# RadioPanel.net
KiCad netlist of a schematic drawn in EAGLE
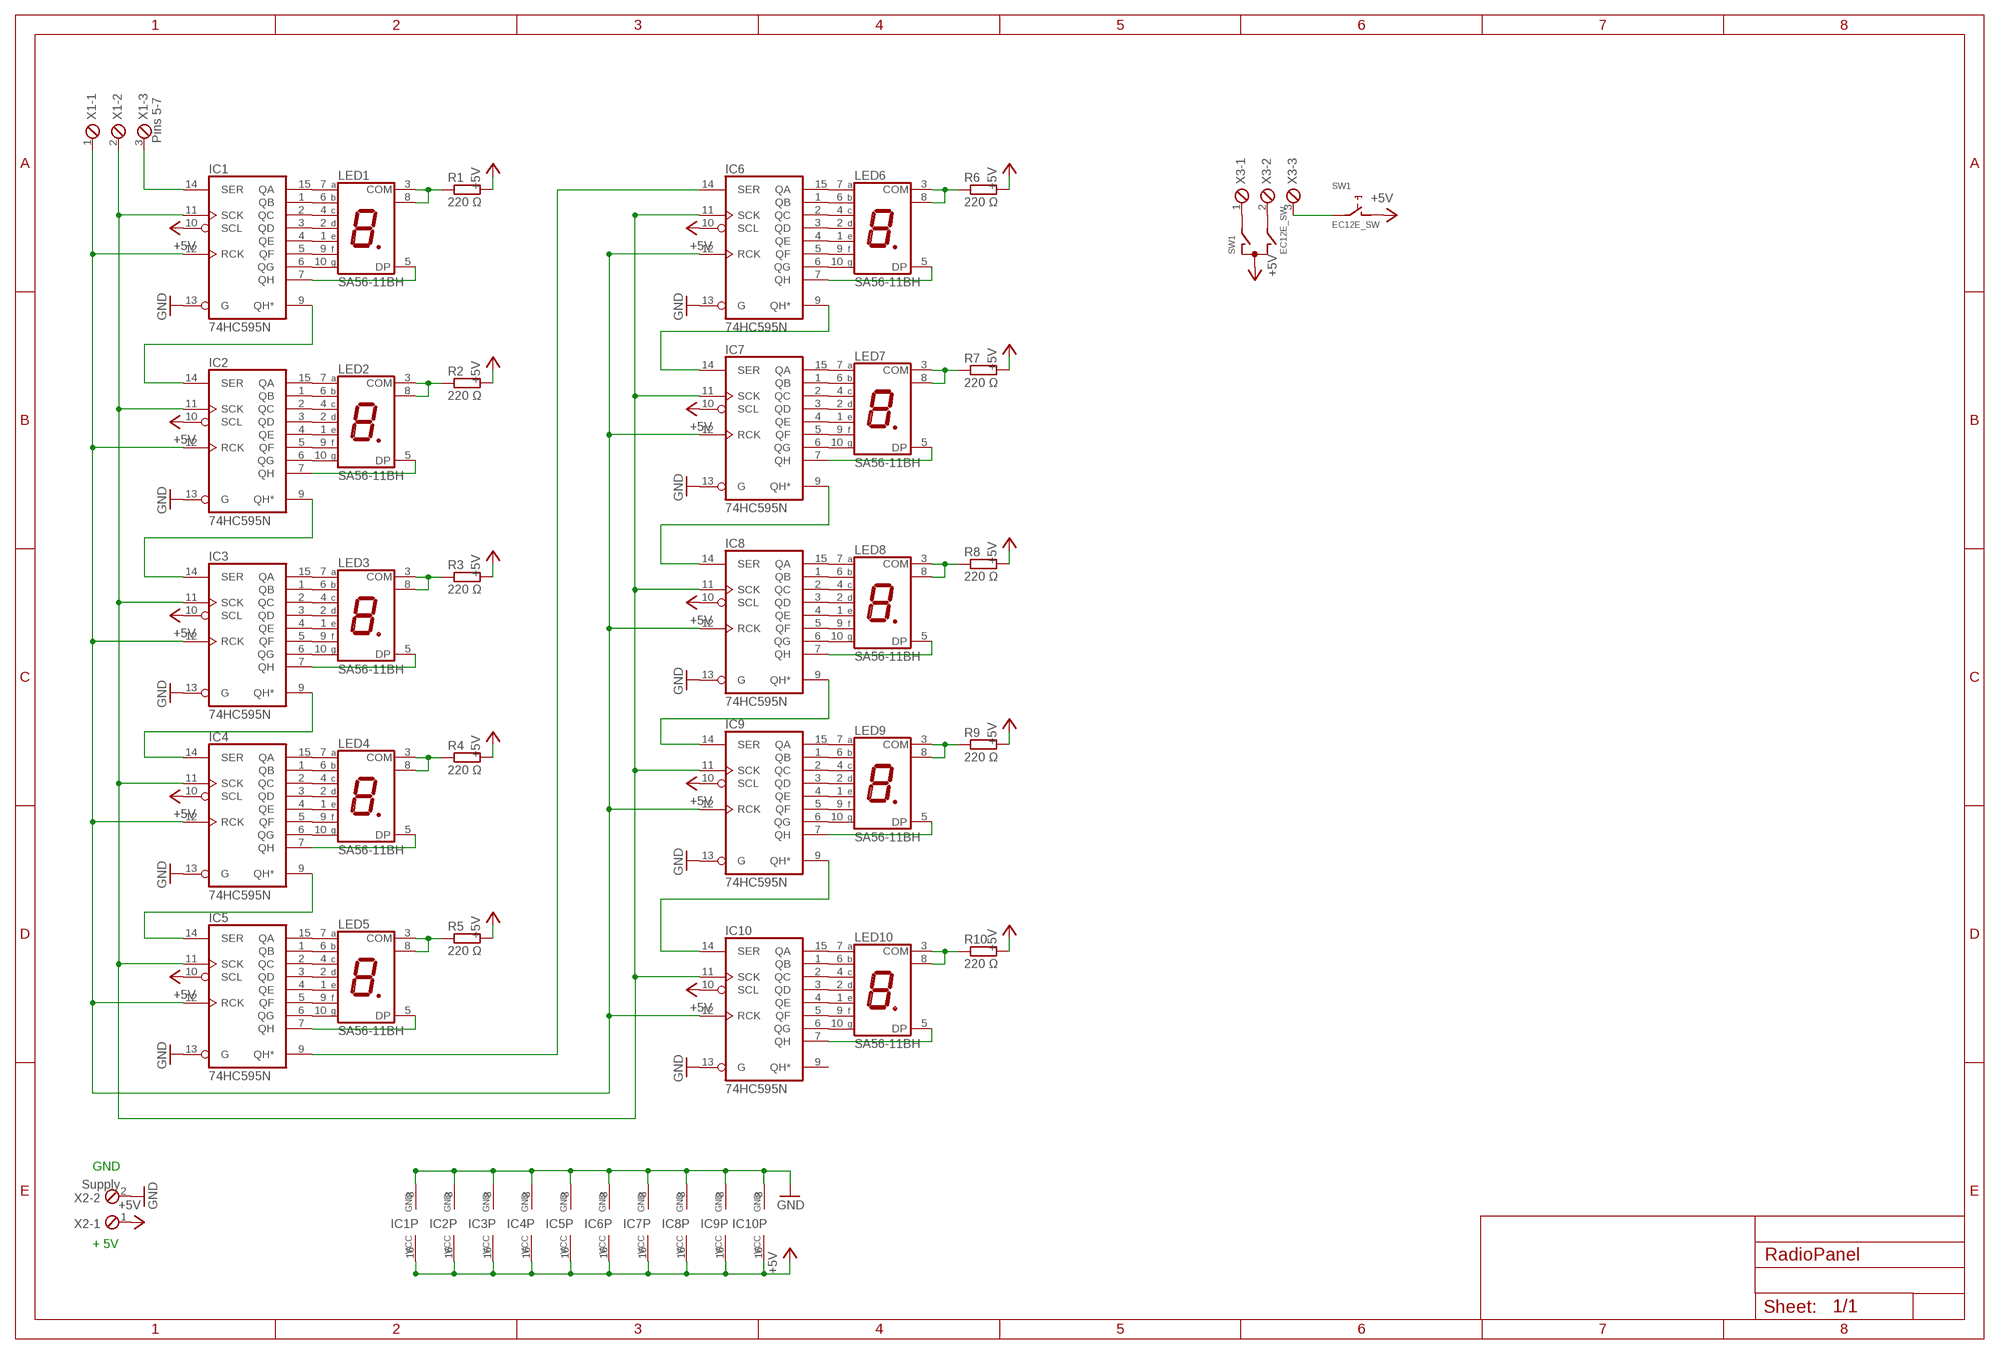
[diagram p0: schematic, sheet 1]

(export (version "E")
  (design (tool "Eeschema 10.0.6"))
  (components
    (comp (ref "IC1")
      (value "74HC595N")
      (footprint "eagle-import:DIL16")
      (libsource (lib "eagle-import") (part "74595NHC"))
    )
    (comp (ref "IC2")
      (value "74HC595N")
      (footprint "eagle-import:DIL16")
      (libsource (lib "eagle-import") (part "74595NHC"))
    )
    (comp (ref "IC3")
      (value "74HC595N")
      (footprint "eagle-import:DIL16")
      (libsource (lib "eagle-import") (part "74595NHC"))
    )
    (comp (ref "IC4")
      (value "74HC595N")
      (footprint "eagle-import:DIL16")
      (libsource (lib "eagle-import") (part "74595NHC"))
    )
    (comp (ref "IC5")
      (value "74HC595N")
      (footprint "eagle-import:DIL16")
      (libsource (lib "eagle-import") (part "74595NHC"))
    )
    (comp (ref "IC6")
      (value "74HC595N")
      (footprint "eagle-import:DIL16")
      (libsource (lib "eagle-import") (part "74595NHC"))
    )
    (comp (ref "IC7")
      (value "74HC595N")
      (footprint "eagle-import:DIL16")
      (libsource (lib "eagle-import") (part "74595NHC"))
    )
    (comp (ref "IC8")
      (value "74HC595N")
      (footprint "eagle-import:DIL16")
      (libsource (lib "eagle-import") (part "74595NHC"))
    )
    (comp (ref "IC9")
      (value "74HC595N")
      (footprint "eagle-import:DIL16")
      (libsource (lib "eagle-import") (part "74595NHC"))
    )
    (comp (ref "IC10")
      (value "74HC595N")
      (footprint "eagle-import:DIL16")
      (libsource (lib "eagle-import") (part "74595NHC"))
    )
    (comp (ref "LED1")
      (value "SA56-11BH")
      (footprint "eagle-import:SA56-11")
      (libsource (lib "eagle-import") (part "7-SEG_SA56-11"))
    )
    (comp (ref "LED2")
      (value "SA56-11BH")
      (footprint "eagle-import:SA56-11")
      (libsource (lib "eagle-import") (part "7-SEG_SA56-11"))
    )
    (comp (ref "LED3")
      (value "SA56-11BH")
      (footprint "eagle-import:SA56-11")
      (libsource (lib "eagle-import") (part "7-SEG_SA56-11"))
    )
    (comp (ref "LED4")
      (value "SA56-11BH")
      (footprint "eagle-import:SA56-11")
      (libsource (lib "eagle-import") (part "7-SEG_SA56-11"))
    )
    (comp (ref "LED5")
      (value "SA56-11BH")
      (footprint "eagle-import:SA56-11")
      (libsource (lib "eagle-import") (part "7-SEG_SA56-11"))
    )
    (comp (ref "LED6")
      (value "SA56-11BH")
      (footprint "eagle-import:SA56-11")
      (libsource (lib "eagle-import") (part "7-SEG_SA56-11"))
    )
    (comp (ref "LED7")
      (value "SA56-11BH")
      (footprint "eagle-import:SA56-11")
      (libsource (lib "eagle-import") (part "7-SEG_SA56-11"))
    )
    (comp (ref "LED8")
      (value "SA56-11BH")
      (footprint "eagle-import:SA56-11")
      (libsource (lib "eagle-import") (part "7-SEG_SA56-11"))
    )
    (comp (ref "LED9")
      (value "SA56-11BH")
      (footprint "eagle-import:SA56-11")
      (libsource (lib "eagle-import") (part "7-SEG_SA56-11"))
    )
    (comp (ref "LED10")
      (value "SA56-11BH")
      (footprint "eagle-import:SA56-11")
      (libsource (lib "eagle-import") (part "7-SEG_SA56-11"))
    )
    (comp (ref "R1")
      (value "220 Ω")
      (footprint "eagle-import:0207_12")
      (libsource (lib "eagle-import") (part "R-EU_0207/12"))
    )
    (comp (ref "R2")
      (value "220 Ω")
      (footprint "eagle-import:0207_12")
      (libsource (lib "eagle-import") (part "R-EU_0207/12"))
    )
    (comp (ref "R3")
      (value "220 Ω")
      (footprint "eagle-import:0207_12")
      (libsource (lib "eagle-import") (part "R-EU_0207/12"))
    )
    (comp (ref "R4")
      (value "220 Ω")
      (footprint "eagle-import:0207_12")
      (libsource (lib "eagle-import") (part "R-EU_0207/12"))
    )
    (comp (ref "R5")
      (value "220 Ω")
      (footprint "eagle-import:0207_12")
      (libsource (lib "eagle-import") (part "R-EU_0207/12"))
    )
    (comp (ref "R6")
      (value "220 Ω")
      (footprint "eagle-import:0207_12")
      (libsource (lib "eagle-import") (part "R-EU_0207/12"))
    )
    (comp (ref "R7")
      (value "220 Ω")
      (footprint "eagle-import:0207_12")
      (libsource (lib "eagle-import") (part "R-EU_0207/12"))
    )
    (comp (ref "R8")
      (value "220 Ω")
      (footprint "eagle-import:0207_12")
      (libsource (lib "eagle-import") (part "R-EU_0207/12"))
    )
    (comp (ref "R9")
      (value "220 Ω")
      (footprint "eagle-import:0207_12")
      (libsource (lib "eagle-import") (part "R-EU_0207/12"))
    )
    (comp (ref "R10")
      (value "220 Ω")
      (footprint "eagle-import:0207_12")
      (libsource (lib "eagle-import") (part "R-EU_0207/12"))
    )
    (comp (ref "SW1")
      (value "EC12E_SW")
      (footprint "eagle-import:ALPS_EC12E_SW")
      (fields (field (name "MPN") "EC12E2424407"))
      (libsource (lib "eagle-import") (part "EC12E_SW"))
    )
    (comp (ref "X1")
      (value "Pins 5-7")
      (footprint "eagle-import:3POL254")
      (libsource (lib "eagle-import") (part "MPT3"))
    )
    (comp (ref "X2")
      (value "Supply")
      (footprint "eagle-import:2POL254")
      (libsource (lib "eagle-import") (part "MPT2"))
    )
    (comp (ref "X3")
      (value "MPT3")
      (footprint "eagle-import:3POL254")
      (libsource (lib "eagle-import") (part "MPT3"))
    )
  )
  (nets
    (net (code "1") (name "+5V") (class "Default")
      (node (ref "IC1") (pin "10") (pinfunction "SCL_10") (pintype "input"))
      (node (ref "IC1") (pin "16") (pinfunction "VCC_16") (pintype "power_in"))
      (node (ref "IC10") (pin "10") (pinfunction "SCL_10") (pintype "input"))
      (node (ref "IC10") (pin "16") (pinfunction "VCC_16") (pintype "power_in"))
      (node (ref "IC2") (pin "10") (pinfunction "SCL_10") (pintype "input"))
      (node (ref "IC2") (pin "16") (pinfunction "VCC_16") (pintype "power_in"))
      (node (ref "IC3") (pin "10") (pinfunction "SCL_10") (pintype "input"))
      (node (ref "IC3") (pin "16") (pinfunction "VCC_16") (pintype "power_in"))
      (node (ref "IC4") (pin "10") (pinfunction "SCL_10") (pintype "input"))
      (node (ref "IC4") (pin "16") (pinfunction "VCC_16") (pintype "power_in"))
      (node (ref "IC5") (pin "10") (pinfunction "SCL_10") (pintype "input"))
      (node (ref "IC5") (pin "16") (pinfunction "VCC_16") (pintype "power_in"))
      (node (ref "IC6") (pin "10") (pinfunction "SCL_10") (pintype "input"))
      (node (ref "IC6") (pin "16") (pinfunction "VCC_16") (pintype "power_in"))
      (node (ref "IC7") (pin "10") (pinfunction "SCL_10") (pintype "input"))
      (node (ref "IC7") (pin "16") (pinfunction "VCC_16") (pintype "power_in"))
      (node (ref "IC8") (pin "10") (pinfunction "SCL_10") (pintype "input"))
      (node (ref "IC8") (pin "16") (pinfunction "VCC_16") (pintype "power_in"))
      (node (ref "IC9") (pin "10") (pinfunction "SCL_10") (pintype "input"))
      (node (ref "IC9") (pin "16") (pinfunction "VCC_16") (pintype "power_in"))
      (node (ref "R1") (pin "2") (pinfunction "2_2") (pintype "passive"))
      (node (ref "R10") (pin "2") (pinfunction "2_2") (pintype "passive"))
      (node (ref "R2") (pin "2") (pinfunction "2_2") (pintype "passive"))
      (node (ref "R3") (pin "2") (pinfunction "2_2") (pintype "passive"))
      (node (ref "R4") (pin "2") (pinfunction "2_2") (pintype "passive"))
      (node (ref "R5") (pin "2") (pinfunction "2_2") (pintype "passive"))
      (node (ref "R6") (pin "2") (pinfunction "2_2") (pintype "passive"))
      (node (ref "R7") (pin "2") (pinfunction "2_2") (pintype "passive"))
      (node (ref "R8") (pin "2") (pinfunction "2_2") (pintype "passive"))
      (node (ref "R9") (pin "2") (pinfunction "2_2") (pintype "passive"))
      (node (ref "SW1") (pin "C") (pinfunction "C_C") (pintype "passive"))
      (node (ref "SW1") (pin "D") (pinfunction "1_D") (pintype "passive"))
      (node (ref "X2") (pin "1") (pinfunction "1_1") (pintype "passive"))
    )
    (net (code "2") (name "GND") (class "Default")
      (node (ref "IC1") (pin "13") (pinfunction "G_13") (pintype "input"))
      (node (ref "IC1") (pin "8") (pinfunction "GND_8") (pintype "power_in"))
      (node (ref "IC10") (pin "13") (pinfunction "G_13") (pintype "input"))
      (node (ref "IC10") (pin "8") (pinfunction "GND_8") (pintype "power_in"))
      (node (ref "IC2") (pin "13") (pinfunction "G_13") (pintype "input"))
      (node (ref "IC2") (pin "8") (pinfunction "GND_8") (pintype "power_in"))
      (node (ref "IC3") (pin "13") (pinfunction "G_13") (pintype "input"))
      (node (ref "IC3") (pin "8") (pinfunction "GND_8") (pintype "power_in"))
      (node (ref "IC4") (pin "13") (pinfunction "G_13") (pintype "input"))
      (node (ref "IC4") (pin "8") (pinfunction "GND_8") (pintype "power_in"))
      (node (ref "IC5") (pin "13") (pinfunction "G_13") (pintype "input"))
      (node (ref "IC5") (pin "8") (pinfunction "GND_8") (pintype "power_in"))
      (node (ref "IC6") (pin "13") (pinfunction "G_13") (pintype "input"))
      (node (ref "IC6") (pin "8") (pinfunction "GND_8") (pintype "power_in"))
      (node (ref "IC7") (pin "13") (pinfunction "G_13") (pintype "input"))
      (node (ref "IC7") (pin "8") (pinfunction "GND_8") (pintype "power_in"))
      (node (ref "IC8") (pin "13") (pinfunction "G_13") (pintype "input"))
      (node (ref "IC8") (pin "8") (pinfunction "GND_8") (pintype "power_in"))
      (node (ref "IC9") (pin "13") (pinfunction "G_13") (pintype "input"))
      (node (ref "IC9") (pin "8") (pinfunction "GND_8") (pintype "power_in"))
      (node (ref "X2") (pin "2") (pinfunction "1_2") (pintype "passive"))
    )
    (net (code "3") (name "Net-(IC1A-QA)") (class "Default")
      (node (ref "IC1") (pin "15") (pinfunction "QA_15") (pintype "tri_state"))
      (node (ref "LED1") (pin "7") (pinfunction "A_7") (pintype "passive"))
    )
    (net (code "4") (name "Net-(IC1A-QB)") (class "Default")
      (node (ref "IC1") (pin "1") (pinfunction "QB_1") (pintype "tri_state"))
      (node (ref "LED1") (pin "6") (pinfunction "B_6") (pintype "passive"))
    )
    (net (code "5") (name "Net-(IC1A-QC)") (class "Default")
      (node (ref "IC1") (pin "2") (pinfunction "QC_2") (pintype "tri_state"))
      (node (ref "LED1") (pin "4") (pinfunction "C_4") (pintype "passive"))
    )
    (net (code "6") (name "Net-(IC1A-QD)") (class "Default")
      (node (ref "IC1") (pin "3") (pinfunction "QD_3") (pintype "tri_state"))
      (node (ref "LED1") (pin "2") (pinfunction "D_2") (pintype "passive"))
    )
    (net (code "7") (name "Net-(IC1A-QE)") (class "Default")
      (node (ref "IC1") (pin "4") (pinfunction "QE_4") (pintype "tri_state"))
      (node (ref "LED1") (pin "1") (pinfunction "E_1") (pintype "passive"))
    )
    (net (code "8") (name "Net-(IC1A-QF)") (class "Default")
      (node (ref "IC1") (pin "5") (pinfunction "QF_5") (pintype "tri_state"))
      (node (ref "LED1") (pin "9") (pinfunction "F_9") (pintype "passive"))
    )
    (net (code "9") (name "Net-(IC1A-QG)") (class "Default")
      (node (ref "IC1") (pin "6") (pinfunction "QG_6") (pintype "tri_state"))
      (node (ref "LED1") (pin "10") (pinfunction "G_10") (pintype "passive"))
    )
    (net (code "10") (name "Net-(IC1A-QH)") (class "Default")
      (node (ref "IC1") (pin "7") (pinfunction "QH_7") (pintype "tri_state"))
      (node (ref "LED1") (pin "5") (pinfunction "DP_5") (pintype "passive"))
    )
    (net (code "11") (name "Net-(IC1A-QH*)") (class "Default")
      (node (ref "IC1") (pin "9") (pinfunction "QH*_9") (pintype "tri_state"))
      (node (ref "IC2") (pin "14") (pinfunction "SER_14") (pintype "input"))
    )
    (net (code "12") (name "Net-(IC1A-SER)") (class "Default")
      (node (ref "IC1") (pin "14") (pinfunction "SER_14") (pintype "input"))
      (node (ref "X1") (pin "3") (pinfunction "1_3") (pintype "passive"))
    )
    (net (code "13") (name "Net-(IC2A-QA)") (class "Default")
      (node (ref "IC2") (pin "15") (pinfunction "QA_15") (pintype "tri_state"))
      (node (ref "LED2") (pin "7") (pinfunction "A_7") (pintype "passive"))
    )
    (net (code "14") (name "Net-(IC2A-QB)") (class "Default")
      (node (ref "IC2") (pin "1") (pinfunction "QB_1") (pintype "tri_state"))
      (node (ref "LED2") (pin "6") (pinfunction "B_6") (pintype "passive"))
    )
    (net (code "15") (name "Net-(IC2A-QC)") (class "Default")
      (node (ref "IC2") (pin "2") (pinfunction "QC_2") (pintype "tri_state"))
      (node (ref "LED2") (pin "4") (pinfunction "C_4") (pintype "passive"))
    )
    (net (code "16") (name "Net-(IC2A-QD)") (class "Default")
      (node (ref "IC2") (pin "3") (pinfunction "QD_3") (pintype "tri_state"))
      (node (ref "LED2") (pin "2") (pinfunction "D_2") (pintype "passive"))
    )
    (net (code "17") (name "Net-(IC2A-QE)") (class "Default")
      (node (ref "IC2") (pin "4") (pinfunction "QE_4") (pintype "tri_state"))
      (node (ref "LED2") (pin "1") (pinfunction "E_1") (pintype "passive"))
    )
    (net (code "18") (name "Net-(IC2A-QF)") (class "Default")
      (node (ref "IC2") (pin "5") (pinfunction "QF_5") (pintype "tri_state"))
      (node (ref "LED2") (pin "9") (pinfunction "F_9") (pintype "passive"))
    )
    (net (code "19") (name "Net-(IC2A-QG)") (class "Default")
      (node (ref "IC2") (pin "6") (pinfunction "QG_6") (pintype "tri_state"))
      (node (ref "LED2") (pin "10") (pinfunction "G_10") (pintype "passive"))
    )
    (net (code "20") (name "Net-(IC2A-QH)") (class "Default")
      (node (ref "IC2") (pin "7") (pinfunction "QH_7") (pintype "tri_state"))
      (node (ref "LED2") (pin "5") (pinfunction "DP_5") (pintype "passive"))
    )
    (net (code "21") (name "Net-(IC2A-QH*)") (class "Default")
      (node (ref "IC2") (pin "9") (pinfunction "QH*_9") (pintype "tri_state"))
      (node (ref "IC3") (pin "14") (pinfunction "SER_14") (pintype "input"))
    )
    (net (code "22") (name "Net-(IC3A-QA)") (class "Default")
      (node (ref "IC3") (pin "15") (pinfunction "QA_15") (pintype "tri_state"))
      (node (ref "LED3") (pin "7") (pinfunction "A_7") (pintype "passive"))
    )
    (net (code "23") (name "Net-(IC3A-QB)") (class "Default")
      (node (ref "IC3") (pin "1") (pinfunction "QB_1") (pintype "tri_state"))
      (node (ref "LED3") (pin "6") (pinfunction "B_6") (pintype "passive"))
    )
    (net (code "24") (name "Net-(IC3A-QC)") (class "Default")
      (node (ref "IC3") (pin "2") (pinfunction "QC_2") (pintype "tri_state"))
      (node (ref "LED3") (pin "4") (pinfunction "C_4") (pintype "passive"))
    )
    (net (code "25") (name "Net-(IC3A-QD)") (class "Default")
      (node (ref "IC3") (pin "3") (pinfunction "QD_3") (pintype "tri_state"))
      (node (ref "LED3") (pin "2") (pinfunction "D_2") (pintype "passive"))
    )
    (net (code "26") (name "Net-(IC3A-QE)") (class "Default")
      (node (ref "IC3") (pin "4") (pinfunction "QE_4") (pintype "tri_state"))
      (node (ref "LED3") (pin "1") (pinfunction "E_1") (pintype "passive"))
    )
    (net (code "27") (name "Net-(IC3A-QF)") (class "Default")
      (node (ref "IC3") (pin "5") (pinfunction "QF_5") (pintype "tri_state"))
      (node (ref "LED3") (pin "9") (pinfunction "F_9") (pintype "passive"))
    )
    (net (code "28") (name "Net-(IC3A-QG)") (class "Default")
      (node (ref "IC3") (pin "6") (pinfunction "QG_6") (pintype "tri_state"))
      (node (ref "LED3") (pin "10") (pinfunction "G_10") (pintype "passive"))
    )
    (net (code "29") (name "Net-(IC3A-QH)") (class "Default")
      (node (ref "IC3") (pin "7") (pinfunction "QH_7") (pintype "tri_state"))
      (node (ref "LED3") (pin "5") (pinfunction "DP_5") (pintype "passive"))
    )
    (net (code "30") (name "Net-(IC3A-QH*)") (class "Default")
      (node (ref "IC3") (pin "9") (pinfunction "QH*_9") (pintype "tri_state"))
      (node (ref "IC4") (pin "14") (pinfunction "SER_14") (pintype "input"))
    )
    (net (code "31") (name "Net-(IC4A-QA)") (class "Default")
      (node (ref "IC4") (pin "15") (pinfunction "QA_15") (pintype "tri_state"))
      (node (ref "LED4") (pin "7") (pinfunction "A_7") (pintype "passive"))
    )
    (net (code "32") (name "Net-(IC4A-QB)") (class "Default")
      (node (ref "IC4") (pin "1") (pinfunction "QB_1") (pintype "tri_state"))
      (node (ref "LED4") (pin "6") (pinfunction "B_6") (pintype "passive"))
    )
    (net (code "33") (name "Net-(IC4A-QC)") (class "Default")
      (node (ref "IC4") (pin "2") (pinfunction "QC_2") (pintype "tri_state"))
      (node (ref "LED4") (pin "4") (pinfunction "C_4") (pintype "passive"))
    )
    (net (code "34") (name "Net-(IC4A-QD)") (class "Default")
      (node (ref "IC4") (pin "3") (pinfunction "QD_3") (pintype "tri_state"))
      (node (ref "LED4") (pin "2") (pinfunction "D_2") (pintype "passive"))
    )
    (net (code "35") (name "Net-(IC4A-QE)") (class "Default")
      (node (ref "IC4") (pin "4") (pinfunction "QE_4") (pintype "tri_state"))
      (node (ref "LED4") (pin "1") (pinfunction "E_1") (pintype "passive"))
    )
    (net (code "36") (name "Net-(IC4A-QF)") (class "Default")
      (node (ref "IC4") (pin "5") (pinfunction "QF_5") (pintype "tri_state"))
      (node (ref "LED4") (pin "9") (pinfunction "F_9") (pintype "passive"))
    )
    (net (code "37") (name "Net-(IC4A-QG)") (class "Default")
      (node (ref "IC4") (pin "6") (pinfunction "QG_6") (pintype "tri_state"))
      (node (ref "LED4") (pin "10") (pinfunction "G_10") (pintype "passive"))
    )
    (net (code "38") (name "Net-(IC4A-QH)") (class "Default")
      (node (ref "IC4") (pin "7") (pinfunction "QH_7") (pintype "tri_state"))
      (node (ref "LED4") (pin "5") (pinfunction "DP_5") (pintype "passive"))
    )
    (net (code "39") (name "Net-(IC4A-QH*)") (class "Default")
      (node (ref "IC4") (pin "9") (pinfunction "QH*_9") (pintype "tri_state"))
      (node (ref "IC5") (pin "14") (pinfunction "SER_14") (pintype "input"))
    )
    (net (code "40") (name "Net-(IC5A-QA)") (class "Default")
      (node (ref "IC5") (pin "15") (pinfunction "QA_15") (pintype "tri_state"))
      (node (ref "LED5") (pin "7") (pinfunction "A_7") (pintype "passive"))
    )
    (net (code "41") (name "Net-(IC5A-QB)") (class "Default")
      (node (ref "IC5") (pin "1") (pinfunction "QB_1") (pintype "tri_state"))
      (node (ref "LED5") (pin "6") (pinfunction "B_6") (pintype "passive"))
    )
    (net (code "42") (name "Net-(IC5A-QC)") (class "Default")
      (node (ref "IC5") (pin "2") (pinfunction "QC_2") (pintype "tri_state"))
      (node (ref "LED5") (pin "4") (pinfunction "C_4") (pintype "passive"))
    )
    (net (code "43") (name "Net-(IC5A-QD)") (class "Default")
      (node (ref "IC5") (pin "3") (pinfunction "QD_3") (pintype "tri_state"))
      (node (ref "LED5") (pin "2") (pinfunction "D_2") (pintype "passive"))
    )
    (net (code "44") (name "Net-(IC5A-QE)") (class "Default")
      (node (ref "IC5") (pin "4") (pinfunction "QE_4") (pintype "tri_state"))
      (node (ref "LED5") (pin "1") (pinfunction "E_1") (pintype "passive"))
    )
    (net (code "45") (name "Net-(IC5A-QF)") (class "Default")
      (node (ref "IC5") (pin "5") (pinfunction "QF_5") (pintype "tri_state"))
      (node (ref "LED5") (pin "9") (pinfunction "F_9") (pintype "passive"))
    )
    (net (code "46") (name "Net-(IC5A-QG)") (class "Default")
      (node (ref "IC5") (pin "6") (pinfunction "QG_6") (pintype "tri_state"))
      (node (ref "LED5") (pin "10") (pinfunction "G_10") (pintype "passive"))
    )
    (net (code "47") (name "Net-(IC5A-QH)") (class "Default")
      (node (ref "IC5") (pin "7") (pinfunction "QH_7") (pintype "tri_state"))
      (node (ref "LED5") (pin "5") (pinfunction "DP_5") (pintype "passive"))
    )
    (net (code "48") (name "Net-(IC5A-QH*)") (class "Default")
      (node (ref "IC5") (pin "9") (pinfunction "QH*_9") (pintype "tri_state"))
      (node (ref "IC6") (pin "14") (pinfunction "SER_14") (pintype "input"))
    )
    (net (code "49") (name "Net-(IC6A-QA)") (class "Default")
      (node (ref "IC6") (pin "15") (pinfunction "QA_15") (pintype "tri_state"))
      (node (ref "LED6") (pin "7") (pinfunction "A_7") (pintype "passive"))
    )
    (net (code "50") (name "Net-(IC6A-QB)") (class "Default")
      (node (ref "IC6") (pin "1") (pinfunction "QB_1") (pintype "tri_state"))
      (node (ref "LED6") (pin "6") (pinfunction "B_6") (pintype "passive"))
    )
    (net (code "51") (name "Net-(IC6A-QC)") (class "Default")
      (node (ref "IC6") (pin "2") (pinfunction "QC_2") (pintype "tri_state"))
      (node (ref "LED6") (pin "4") (pinfunction "C_4") (pintype "passive"))
    )
    (net (code "52") (name "Net-(IC6A-QD)") (class "Default")
      (node (ref "IC6") (pin "3") (pinfunction "QD_3") (pintype "tri_state"))
      (node (ref "LED6") (pin "2") (pinfunction "D_2") (pintype "passive"))
    )
    (net (code "53") (name "Net-(IC6A-QE)") (class "Default")
      (node (ref "IC6") (pin "4") (pinfunction "QE_4") (pintype "tri_state"))
      (node (ref "LED6") (pin "1") (pinfunction "E_1") (pintype "passive"))
    )
    (net (code "54") (name "Net-(IC6A-QF)") (class "Default")
      (node (ref "IC6") (pin "5") (pinfunction "QF_5") (pintype "tri_state"))
      (node (ref "LED6") (pin "9") (pinfunction "F_9") (pintype "passive"))
    )
    (net (code "55") (name "Net-(IC6A-QG)") (class "Default")
      (node (ref "IC6") (pin "6") (pinfunction "QG_6") (pintype "tri_state"))
      (node (ref "LED6") (pin "10") (pinfunction "G_10") (pintype "passive"))
    )
    (net (code "56") (name "Net-(IC6A-QH)") (class "Default")
      (node (ref "IC6") (pin "7") (pinfunction "QH_7") (pintype "tri_state"))
      (node (ref "LED6") (pin "5") (pinfunction "DP_5") (pintype "passive"))
    )
    (net (code "57") (name "Net-(IC6A-QH*)") (class "Default")
      (node (ref "IC6") (pin "9") (pinfunction "QH*_9") (pintype "tri_state"))
      (node (ref "IC7") (pin "14") (pinfunction "SER_14") (pintype "input"))
    )
    (net (code "58") (name "Net-(IC7A-QA)") (class "Default")
      (node (ref "IC7") (pin "15") (pinfunction "QA_15") (pintype "tri_state"))
      (node (ref "LED7") (pin "7") (pinfunction "A_7") (pintype "passive"))
    )
    (net (code "59") (name "Net-(IC7A-QB)") (class "Default")
      (node (ref "IC7") (pin "1") (pinfunction "QB_1") (pintype "tri_state"))
      (node (ref "LED7") (pin "6") (pinfunction "B_6") (pintype "passive"))
    )
    (net (code "60") (name "Net-(IC7A-QC)") (class "Default")
      (node (ref "IC7") (pin "2") (pinfunction "QC_2") (pintype "tri_state"))
      (node (ref "LED7") (pin "4") (pinfunction "C_4") (pintype "passive"))
    )
    (net (code "61") (name "Net-(IC7A-QD)") (class "Default")
      (node (ref "IC7") (pin "3") (pinfunction "QD_3") (pintype "tri_state"))
      (node (ref "LED7") (pin "2") (pinfunction "D_2") (pintype "passive"))
    )
    (net (code "62") (name "Net-(IC7A-QE)") (class "Default")
      (node (ref "IC7") (pin "4") (pinfunction "QE_4") (pintype "tri_state"))
      (node (ref "LED7") (pin "1") (pinfunction "E_1") (pintype "passive"))
    )
    (net (code "63") (name "Net-(IC7A-QF)") (class "Default")
      (node (ref "IC7") (pin "5") (pinfunction "QF_5") (pintype "tri_state"))
      (node (ref "LED7") (pin "9") (pinfunction "F_9") (pintype "passive"))
    )
    (net (code "64") (name "Net-(IC7A-QG)") (class "Default")
      (node (ref "IC7") (pin "6") (pinfunction "QG_6") (pintype "tri_state"))
      (node (ref "LED7") (pin "10") (pinfunction "G_10") (pintype "passive"))
    )
    (net (code "65") (name "Net-(IC7A-QH)") (class "Default")
      (node (ref "IC7") (pin "7") (pinfunction "QH_7") (pintype "tri_state"))
      (node (ref "LED7") (pin "5") (pinfunction "DP_5") (pintype "passive"))
    )
    (net (code "66") (name "Net-(IC7A-QH*)") (class "Default")
      (node (ref "IC7") (pin "9") (pinfunction "QH*_9") (pintype "tri_state"))
      (node (ref "IC8") (pin "14") (pinfunction "SER_14") (pintype "input"))
    )
    (net (code "67") (name "Net-(IC8A-QA)") (class "Default")
      (node (ref "IC8") (pin "15") (pinfunction "QA_15") (pintype "tri_state"))
      (node (ref "LED8") (pin "7") (pinfunction "A_7") (pintype "passive"))
    )
    (net (code "68") (name "Net-(IC8A-QB)") (class "Default")
      (node (ref "IC8") (pin "1") (pinfunction "QB_1") (pintype "tri_state"))
      (node (ref "LED8") (pin "6") (pinfunction "B_6") (pintype "passive"))
    )
    (net (code "69") (name "Net-(IC8A-QC)") (class "Default")
      (node (ref "IC8") (pin "2") (pinfunction "QC_2") (pintype "tri_state"))
      (node (ref "LED8") (pin "4") (pinfunction "C_4") (pintype "passive"))
    )
    (net (code "70") (name "Net-(IC8A-QD)") (class "Default")
      (node (ref "IC8") (pin "3") (pinfunction "QD_3") (pintype "tri_state"))
      (node (ref "LED8") (pin "2") (pinfunction "D_2") (pintype "passive"))
    )
    (net (code "71") (name "Net-(IC8A-QE)") (class "Default")
      (node (ref "IC8") (pin "4") (pinfunction "QE_4") (pintype "tri_state"))
      (node (ref "LED8") (pin "1") (pinfunction "E_1") (pintype "passive"))
    )
    (net (code "72") (name "Net-(IC8A-QF)") (class "Default")
      (node (ref "IC8") (pin "5") (pinfunction "QF_5") (pintype "tri_state"))
      (node (ref "LED8") (pin "9") (pinfunction "F_9") (pintype "passive"))
    )
    (net (code "73") (name "Net-(IC8A-QG)") (class "Default")
      (node (ref "IC8") (pin "6") (pinfunction "QG_6") (pintype "tri_state"))
      (node (ref "LED8") (pin "10") (pinfunction "G_10") (pintype "passive"))
    )
    (net (code "74") (name "Net-(IC8A-QH)") (class "Default")
      (node (ref "IC8") (pin "7") (pinfunction "QH_7") (pintype "tri_state"))
      (node (ref "LED8") (pin "5") (pinfunction "DP_5") (pintype "passive"))
    )
    (net (code "75") (name "Net-(IC8A-QH*)") (class "Default")
      (node (ref "IC8") (pin "9") (pinfunction "QH*_9") (pintype "tri_state"))
      (node (ref "IC9") (pin "14") (pinfunction "SER_14") (pintype "input"))
    )
    (net (code "76") (name "Net-(IC9A-QA)") (class "Default")
      (node (ref "IC9") (pin "15") (pinfunction "QA_15") (pintype "tri_state"))
      (node (ref "LED9") (pin "7") (pinfunction "A_7") (pintype "passive"))
    )
    (net (code "77") (name "Net-(IC9A-QB)") (class "Default")
      (node (ref "IC9") (pin "1") (pinfunction "QB_1") (pintype "tri_state"))
      (node (ref "LED9") (pin "6") (pinfunction "B_6") (pintype "passive"))
    )
    (net (code "78") (name "Net-(IC9A-QC)") (class "Default")
      (node (ref "IC9") (pin "2") (pinfunction "QC_2") (pintype "tri_state"))
      (node (ref "LED9") (pin "4") (pinfunction "C_4") (pintype "passive"))
    )
    (net (code "79") (name "Net-(IC9A-QD)") (class "Default")
      (node (ref "IC9") (pin "3") (pinfunction "QD_3") (pintype "tri_state"))
      (node (ref "LED9") (pin "2") (pinfunction "D_2") (pintype "passive"))
    )
    (net (code "80") (name "Net-(IC9A-QE)") (class "Default")
      (node (ref "IC9") (pin "4") (pinfunction "QE_4") (pintype "tri_state"))
      (node (ref "LED9") (pin "1") (pinfunction "E_1") (pintype "passive"))
    )
    (net (code "81") (name "Net-(IC9A-QF)") (class "Default")
      (node (ref "IC9") (pin "5") (pinfunction "QF_5") (pintype "tri_state"))
      (node (ref "LED9") (pin "9") (pinfunction "F_9") (pintype "passive"))
    )
    (net (code "82") (name "Net-(IC9A-QG)") (class "Default")
      (node (ref "IC9") (pin "6") (pinfunction "QG_6") (pintype "tri_state"))
      (node (ref "LED9") (pin "10") (pinfunction "G_10") (pintype "passive"))
    )
    (net (code "83") (name "Net-(IC9A-QH)") (class "Default")
      (node (ref "IC9") (pin "7") (pinfunction "QH_7") (pintype "tri_state"))
      (node (ref "LED9") (pin "5") (pinfunction "DP_5") (pintype "passive"))
    )
    (net (code "84") (name "Net-(IC10A-QA)") (class "Default")
      (node (ref "IC10") (pin "15") (pinfunction "QA_15") (pintype "tri_state"))
      (node (ref "LED10") (pin "7") (pinfunction "A_7") (pintype "passive"))
    )
    (net (code "85") (name "Net-(IC10A-QB)") (class "Default")
      (node (ref "IC10") (pin "1") (pinfunction "QB_1") (pintype "tri_state"))
      (node (ref "LED10") (pin "6") (pinfunction "B_6") (pintype "passive"))
    )
    (net (code "86") (name "Net-(IC10A-QC)") (class "Default")
      (node (ref "IC10") (pin "2") (pinfunction "QC_2") (pintype "tri_state"))
      (node (ref "LED10") (pin "4") (pinfunction "C_4") (pintype "passive"))
    )
    (net (code "87") (name "Net-(IC10A-QD)") (class "Default")
      (node (ref "IC10") (pin "3") (pinfunction "QD_3") (pintype "tri_state"))
      (node (ref "LED10") (pin "2") (pinfunction "D_2") (pintype "passive"))
    )
    (net (code "88") (name "Net-(IC10A-QE)") (class "Default")
      (node (ref "IC10") (pin "4") (pinfunction "QE_4") (pintype "tri_state"))
      (node (ref "LED10") (pin "1") (pinfunction "E_1") (pintype "passive"))
    )
    (net (code "89") (name "Net-(IC10A-QF)") (class "Default")
      (node (ref "IC10") (pin "5") (pinfunction "QF_5") (pintype "tri_state"))
      (node (ref "LED10") (pin "9") (pinfunction "F_9") (pintype "passive"))
    )
    (net (code "90") (name "Net-(IC10A-QG)") (class "Default")
      (node (ref "IC10") (pin "6") (pinfunction "QG_6") (pintype "tri_state"))
      (node (ref "LED10") (pin "10") (pinfunction "G_10") (pintype "passive"))
    )
    (net (code "91") (name "Net-(IC10A-QH)") (class "Default")
      (node (ref "IC10") (pin "7") (pinfunction "QH_7") (pintype "tri_state"))
      (node (ref "LED10") (pin "5") (pinfunction "DP_5") (pintype "passive"))
    )
    (net (code "92") (name "Net-(IC10A-RCK)") (class "Default")
      (node (ref "IC1") (pin "12") (pinfunction "RCK_12") (pintype "input"))
      (node (ref "IC10") (pin "12") (pinfunction "RCK_12") (pintype "input"))
      (node (ref "IC2") (pin "12") (pinfunction "RCK_12") (pintype "input"))
      (node (ref "IC3") (pin "12") (pinfunction "RCK_12") (pintype "input"))
      (node (ref "IC4") (pin "12") (pinfunction "RCK_12") (pintype "input"))
      (node (ref "IC5") (pin "12") (pinfunction "RCK_12") (pintype "input"))
      (node (ref "IC6") (pin "12") (pinfunction "RCK_12") (pintype "input"))
      (node (ref "IC7") (pin "12") (pinfunction "RCK_12") (pintype "input"))
      (node (ref "IC8") (pin "12") (pinfunction "RCK_12") (pintype "input"))
      (node (ref "IC9") (pin "12") (pinfunction "RCK_12") (pintype "input"))
      (node (ref "X1") (pin "1") (pinfunction "1_1") (pintype "passive"))
    )
    (net (code "93") (name "Net-(IC10A-SCK)") (class "Default")
      (node (ref "IC1") (pin "11") (pinfunction "SCK_11") (pintype "input"))
      (node (ref "IC10") (pin "11") (pinfunction "SCK_11") (pintype "input"))
      (node (ref "IC2") (pin "11") (pinfunction "SCK_11") (pintype "input"))
      (node (ref "IC3") (pin "11") (pinfunction "SCK_11") (pintype "input"))
      (node (ref "IC4") (pin "11") (pinfunction "SCK_11") (pintype "input"))
      (node (ref "IC5") (pin "11") (pinfunction "SCK_11") (pintype "input"))
      (node (ref "IC6") (pin "11") (pinfunction "SCK_11") (pintype "input"))
      (node (ref "IC7") (pin "11") (pinfunction "SCK_11") (pintype "input"))
      (node (ref "IC8") (pin "11") (pinfunction "SCK_11") (pintype "input"))
      (node (ref "IC9") (pin "11") (pinfunction "SCK_11") (pintype "input"))
      (node (ref "X1") (pin "2") (pinfunction "1_2") (pintype "passive"))
    )
    (net (code "94") (name "Net-(IC10A-SER)") (class "Default")
      (node (ref "IC10") (pin "14") (pinfunction "SER_14") (pintype "input"))
      (node (ref "IC9") (pin "9") (pinfunction "QH*_9") (pintype "tri_state"))
    )
    (net (code "95") (name "Net-(LED1-COM-Pad3)") (class "Default")
      (node (ref "LED1") (pin "3") (pinfunction "COM_3") (pintype "passive"))
      (node (ref "LED1") (pin "8") (pinfunction "COM_8") (pintype "passive"))
      (node (ref "R1") (pin "1") (pinfunction "1_1") (pintype "passive"))
    )
    (net (code "96") (name "Net-(LED2-COM-Pad3)") (class "Default")
      (node (ref "LED2") (pin "3") (pinfunction "COM_3") (pintype "passive"))
      (node (ref "LED2") (pin "8") (pinfunction "COM_8") (pintype "passive"))
      (node (ref "R2") (pin "1") (pinfunction "1_1") (pintype "passive"))
    )
    (net (code "97") (name "Net-(LED3-COM-Pad3)") (class "Default")
      (node (ref "LED3") (pin "3") (pinfunction "COM_3") (pintype "passive"))
      (node (ref "LED3") (pin "8") (pinfunction "COM_8") (pintype "passive"))
      (node (ref "R3") (pin "1") (pinfunction "1_1") (pintype "passive"))
    )
    (net (code "98") (name "Net-(LED4-COM-Pad3)") (class "Default")
      (node (ref "LED4") (pin "3") (pinfunction "COM_3") (pintype "passive"))
      (node (ref "LED4") (pin "8") (pinfunction "COM_8") (pintype "passive"))
      (node (ref "R4") (pin "1") (pinfunction "1_1") (pintype "passive"))
    )
    (net (code "99") (name "Net-(LED5-COM-Pad3)") (class "Default")
      (node (ref "LED5") (pin "3") (pinfunction "COM_3") (pintype "passive"))
      (node (ref "LED5") (pin "8") (pinfunction "COM_8") (pintype "passive"))
      (node (ref "R5") (pin "1") (pinfunction "1_1") (pintype "passive"))
    )
    (net (code "100") (name "Net-(LED6-COM-Pad3)") (class "Default")
      (node (ref "LED6") (pin "3") (pinfunction "COM_3") (pintype "passive"))
      (node (ref "LED6") (pin "8") (pinfunction "COM_8") (pintype "passive"))
      (node (ref "R6") (pin "1") (pinfunction "1_1") (pintype "passive"))
    )
    (net (code "101") (name "Net-(LED7-COM-Pad3)") (class "Default")
      (node (ref "LED7") (pin "3") (pinfunction "COM_3") (pintype "passive"))
      (node (ref "LED7") (pin "8") (pinfunction "COM_8") (pintype "passive"))
      (node (ref "R7") (pin "1") (pinfunction "1_1") (pintype "passive"))
    )
    (net (code "102") (name "Net-(LED8-COM-Pad3)") (class "Default")
      (node (ref "LED8") (pin "3") (pinfunction "COM_3") (pintype "passive"))
      (node (ref "LED8") (pin "8") (pinfunction "COM_8") (pintype "passive"))
      (node (ref "R8") (pin "1") (pinfunction "1_1") (pintype "passive"))
    )
    (net (code "103") (name "Net-(LED9-COM-Pad3)") (class "Default")
      (node (ref "LED9") (pin "3") (pinfunction "COM_3") (pintype "passive"))
      (node (ref "LED9") (pin "8") (pinfunction "COM_8") (pintype "passive"))
      (node (ref "R9") (pin "1") (pinfunction "1_1") (pintype "passive"))
    )
    (net (code "104") (name "Net-(LED10-COM-Pad3)") (class "Default")
      (node (ref "LED10") (pin "3") (pinfunction "COM_3") (pintype "passive"))
      (node (ref "LED10") (pin "8") (pinfunction "COM_8") (pintype "passive"))
      (node (ref "R10") (pin "1") (pinfunction "1_1") (pintype "passive"))
    )
    (net (code "105") (name "Net-(SW1-PadA)") (class "Default")
      (node (ref "SW1") (pin "A") (pinfunction "A_A") (pintype "passive"))
      (node (ref "X3") (pin "1") (pinfunction "1_1") (pintype "passive"))
    )
    (net (code "106") (name "Net-(SW1B-2)") (class "Default")
      (node (ref "SW1") (pin "E") (pinfunction "2_E") (pintype "passive"))
      (node (ref "X3") (pin "3") (pinfunction "1_3") (pintype "passive"))
    )
    (net (code "107") (name "Net-(X3B-1)") (class "Default")
      (node (ref "SW1") (pin "B") (pinfunction "B_B") (pintype "passive"))
      (node (ref "X3") (pin "2") (pinfunction "1_2") (pintype "passive"))
    )
    (net (code "108") (name "unconnected-(IC10A-QH*-Pad9)") (class "Default")
      (node (ref "IC10") (pin "9") (pinfunction "QH*_9") (pintype "tri_state"))
    )
  )
)
